# PowerClocks.net
KiCad netlist of a schematic drawn in Altium Designer
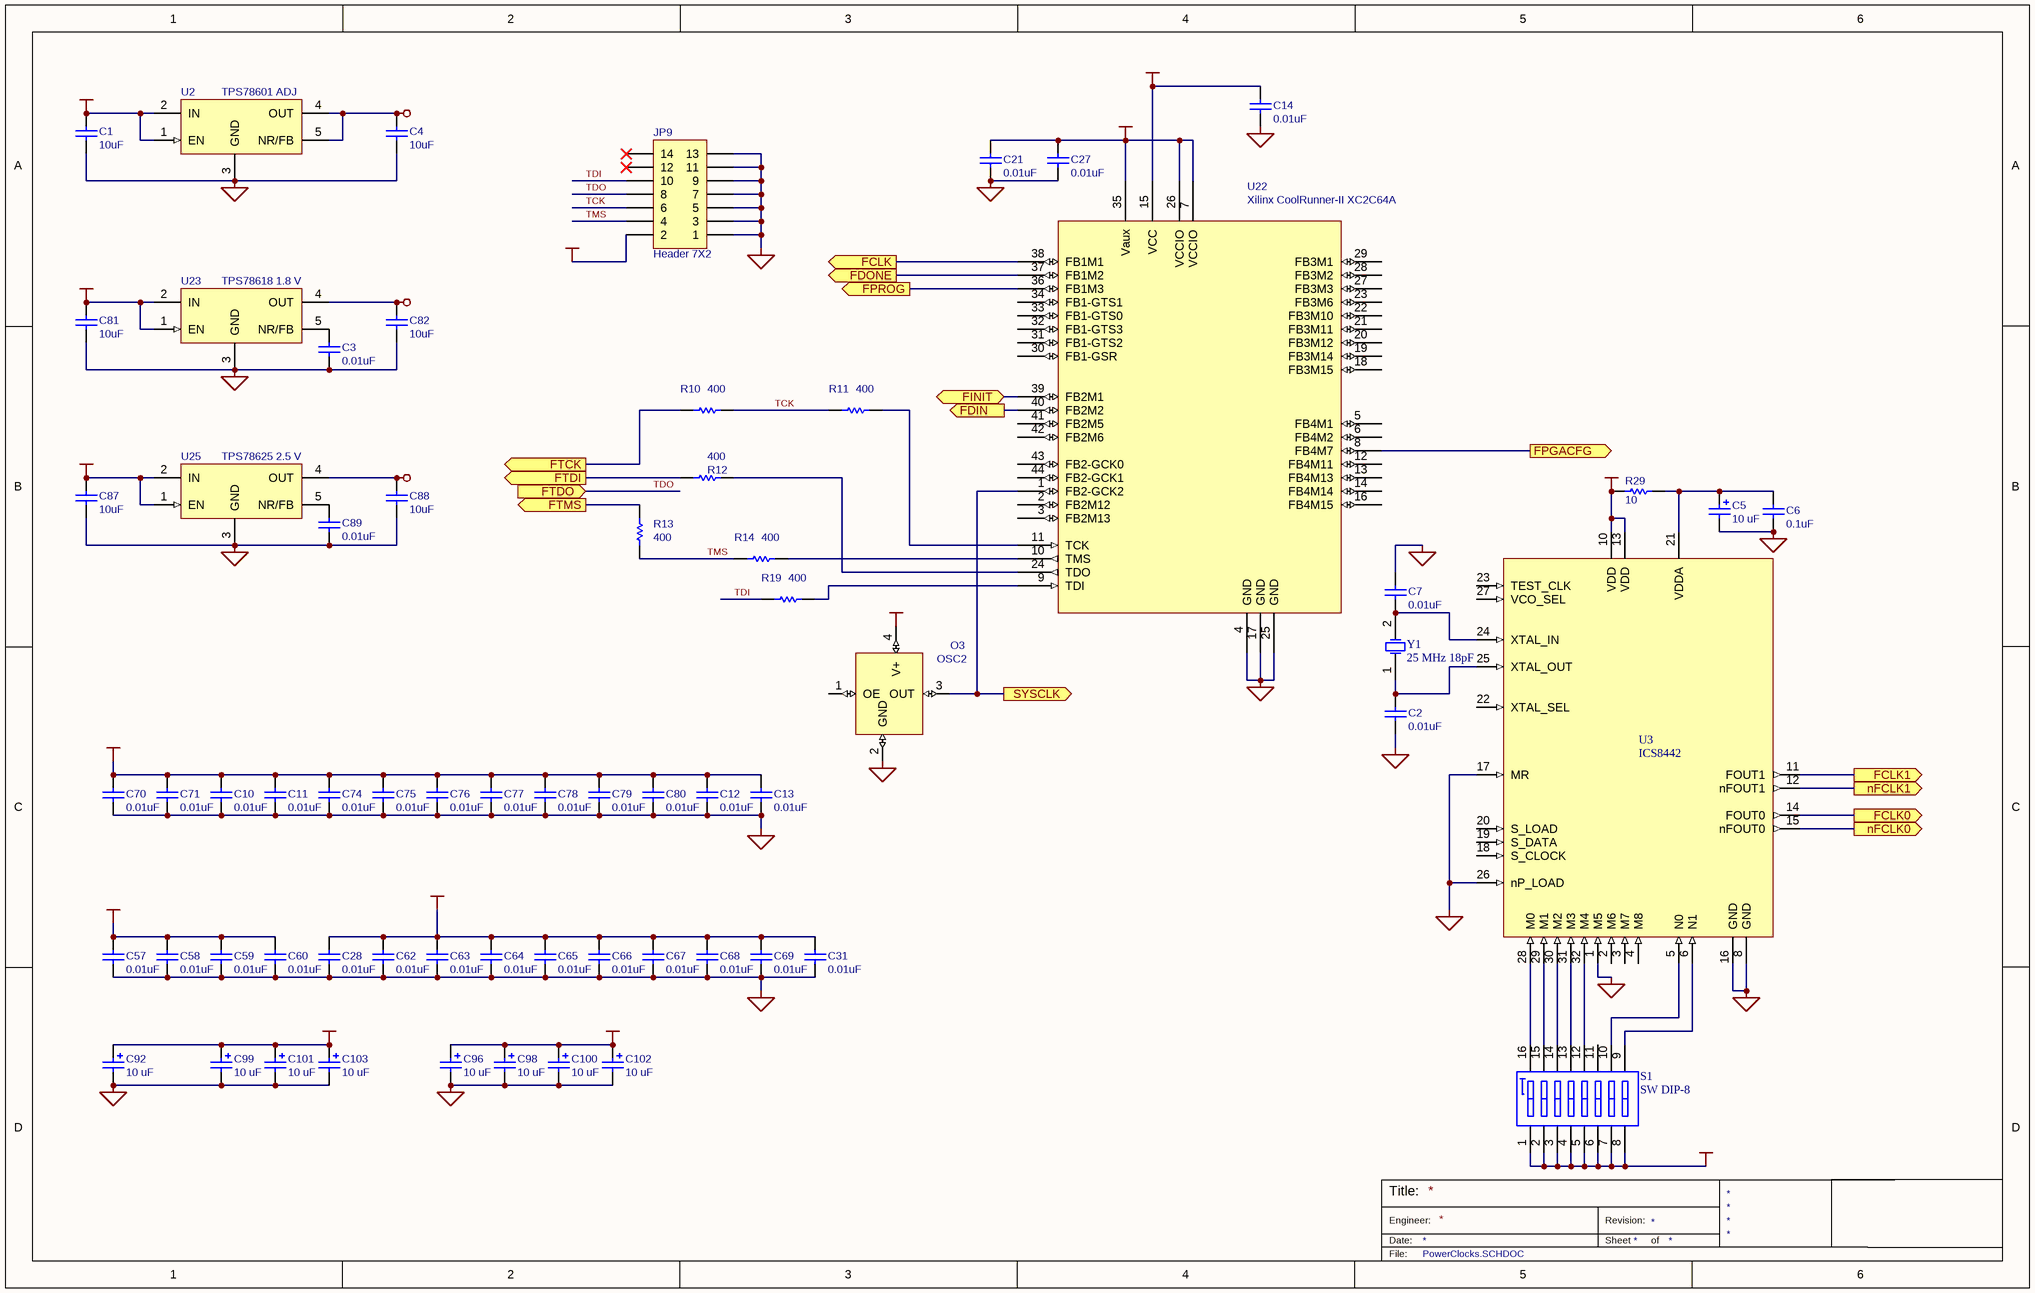
[diagram p0: PowerClocks.SCHDOC]

(export (version "E")
  (design (tool "Eeschema 10.0.6"))
  (components
    (comp (ref "C1")
      (value "10uF")
      (footprint "CC3216-1206")
      (description "Capacitor")
      (fields (field (name "PUBLISHER") "Altium Limited"))
      (libsource (lib "Miscellaneous Devices") (part "Cap"))
    )
    (comp (ref "C2")
      (value "0.01uF")
      (footprint "CC1005-0402")
      (description "Capacitor")
      (fields
        (field (name "MANUFACTURER") "Generic Components")
        (field (name "Comment") "Cap")
        (field (name "PUBLISHER") "Altium Limited")
      )
      (libsource (lib "Miscellaneous Devices") (part "Cap"))
    )
    (comp (ref "C3")
      (value "0.01uF")
      (footprint "CC1005-0402")
      (description "Capacitor")
      (fields (field (name "Comment") "Cap") (field (name "PUBLISHER") "Altium Limited"))
      (libsource (lib "Miscellaneous Devices") (part "Cap"))
    )
    (comp (ref "C4")
      (value "10uF")
      (footprint "CC3216-1206")
      (description "Capacitor")
      (fields (field (name "PUBLISHER") "Altium Limited"))
      (libsource (lib "Miscellaneous Devices") (part "Cap"))
    )
    (comp (ref "C5")
      (value "10 uF")
      (footprint "TC3528-1411")
      (description "Tantalum Bypass cap")
      (fields
        (field (name "MANUFACTURER") "Generic Components")
        (field (name "Comment") "Bypass Cap")
        (field (name "PUBLISHER") "Altium Limited")
      )
      (libsource (lib "Miscellaneous Devices") (part "Cap Pol3"))
    )
    (comp (ref "C6")
      (value "0.1uF")
      (footprint "CC1005-0402")
      (description "Capacitor")
      (fields
        (field (name "MANUFACTURER") "Generic Components")
        (field (name "Comment") "Cap")
        (field (name "PUBLISHER") "Altium Limited")
      )
      (libsource (lib "Miscellaneous Devices") (part "Cap"))
    )
    (comp (ref "C7")
      (value "0.01uF")
      (footprint "CC1005-0402")
      (description "Capacitor")
      (fields
        (field (name "MANUFACTURER") "Generic Components")
        (field (name "Comment") "Cap")
        (field (name "PUBLISHER") "Altium Limited")
      )
      (libsource (lib "Miscellaneous Devices") (part "Cap"))
    )
    (comp (ref "C10")
      (value "0.01uF")
      (footprint "CC1005-0402")
      (description "Capacitor")
      (fields
        (field (name "MANUFACTURER") "Generic Components")
        (field (name "Comment") "Cap")
        (field (name "PUBLISHER") "Altium Limited")
      )
      (libsource (lib "Miscellaneous Devices") (part "Cap"))
    )
    (comp (ref "C11")
      (value "0.01uF")
      (footprint "CC1005-0402")
      (description "Capacitor")
      (fields
        (field (name "MANUFACTURER") "Generic Components")
        (field (name "Comment") "Cap")
        (field (name "PUBLISHER") "Altium Limited")
      )
      (libsource (lib "Miscellaneous Devices") (part "Cap"))
    )
    (comp (ref "C12")
      (value "0.01uF")
      (footprint "CC1005-0402")
      (description "Capacitor")
      (fields
        (field (name "MANUFACTURER") "Generic Components")
        (field (name "Comment") "Cap")
        (field (name "PUBLISHER") "Altium Limited")
      )
      (libsource (lib "Miscellaneous Devices") (part "Cap"))
    )
    (comp (ref "C13")
      (value "0.01uF")
      (footprint "CC1005-0402")
      (description "Capacitor")
      (fields
        (field (name "MANUFACTURER") "Generic Components")
        (field (name "Comment") "Cap")
        (field (name "PUBLISHER") "Altium Limited")
      )
      (libsource (lib "Miscellaneous Devices") (part "Cap"))
    )
    (comp (ref "C14")
      (value "0.01uF")
      (footprint "CC1005-0402")
      (description "Capacitor")
      (fields
        (field (name "MANUFACTURER") "Generic Components")
        (field (name "Comment") "Cap")
        (field (name "PUBLISHER") "Altium Limited")
      )
      (libsource (lib "Miscellaneous Devices") (part "Cap"))
    )
    (comp (ref "C21")
      (value "0.01uF")
      (footprint "CC1005-0402")
      (description "Capacitor")
      (fields
        (field (name "MANUFACTURER") "Generic Components")
        (field (name "Comment") "Cap")
        (field (name "PUBLISHER") "Altium Limited")
      )
      (libsource (lib "Miscellaneous Devices") (part "Cap"))
    )
    (comp (ref "C27")
      (value "0.01uF")
      (footprint "CC1005-0402")
      (description "Capacitor")
      (fields
        (field (name "MANUFACTURER") "Generic Components")
        (field (name "Comment") "Cap")
        (field (name "PUBLISHER") "Altium Limited")
      )
      (libsource (lib "Miscellaneous Devices") (part "Cap"))
    )
    (comp (ref "C28")
      (value "0.01uF")
      (footprint "CC1005-0402")
      (description "Capacitor")
      (fields
        (field (name "MANUFACTURER") "Generic Components")
        (field (name "Comment") "Cap")
        (field (name "PUBLISHER") "Altium Limited")
      )
      (libsource (lib "Miscellaneous Devices") (part "Cap"))
    )
    (comp (ref "C31")
      (value "0.01uF")
      (footprint "CC1005-0402")
      (description "Capacitor")
      (fields
        (field (name "MANUFACTURER") "Generic Components")
        (field (name "Comment") "Cap")
        (field (name "PUBLISHER") "Altium Limited")
      )
      (libsource (lib "Miscellaneous Devices") (part "Cap"))
    )
    (comp (ref "C57")
      (value "0.01uF")
      (footprint "CC1005-0402")
      (description "Capacitor")
      (fields
        (field (name "MANUFACTURER") "Generic Components")
        (field (name "Comment") "Cap")
        (field (name "PUBLISHER") "Altium Limited")
      )
      (libsource (lib "Miscellaneous Devices") (part "Cap"))
    )
    (comp (ref "C58")
      (value "0.01uF")
      (footprint "CC1005-0402")
      (description "Capacitor")
      (fields
        (field (name "MANUFACTURER") "Generic Components")
        (field (name "Comment") "Cap")
        (field (name "PUBLISHER") "Altium Limited")
      )
      (libsource (lib "Miscellaneous Devices") (part "Cap"))
    )
    (comp (ref "C59")
      (value "0.01uF")
      (footprint "CC1005-0402")
      (description "Capacitor")
      (fields
        (field (name "MANUFACTURER") "Generic Components")
        (field (name "Comment") "Cap")
        (field (name "PUBLISHER") "Altium Limited")
      )
      (libsource (lib "Miscellaneous Devices") (part "Cap"))
    )
    (comp (ref "C60")
      (value "0.01uF")
      (footprint "CC1005-0402")
      (description "Capacitor")
      (fields
        (field (name "MANUFACTURER") "Generic Components")
        (field (name "Comment") "Cap")
        (field (name "PUBLISHER") "Altium Limited")
      )
      (libsource (lib "Miscellaneous Devices") (part "Cap"))
    )
    (comp (ref "C62")
      (value "0.01uF")
      (footprint "CC1005-0402")
      (description "Capacitor")
      (fields
        (field (name "MANUFACTURER") "Generic Components")
        (field (name "Comment") "Cap")
        (field (name "PUBLISHER") "Altium Limited")
      )
      (libsource (lib "Miscellaneous Devices") (part "Cap"))
    )
    (comp (ref "C63")
      (value "0.01uF")
      (footprint "CC1005-0402")
      (description "Capacitor")
      (fields
        (field (name "MANUFACTURER") "Generic Components")
        (field (name "Comment") "Cap")
        (field (name "PUBLISHER") "Altium Limited")
      )
      (libsource (lib "Miscellaneous Devices") (part "Cap"))
    )
    (comp (ref "C64")
      (value "0.01uF")
      (footprint "CC1005-0402")
      (description "Capacitor")
      (fields
        (field (name "MANUFACTURER") "Generic Components")
        (field (name "Comment") "Cap")
        (field (name "PUBLISHER") "Altium Limited")
      )
      (libsource (lib "Miscellaneous Devices") (part "Cap"))
    )
    (comp (ref "C65")
      (value "0.01uF")
      (footprint "CC1005-0402")
      (description "Capacitor")
      (fields
        (field (name "MANUFACTURER") "Generic Components")
        (field (name "Comment") "Cap")
        (field (name "PUBLISHER") "Altium Limited")
      )
      (libsource (lib "Miscellaneous Devices") (part "Cap"))
    )
    (comp (ref "C66")
      (value "0.01uF")
      (footprint "CC1005-0402")
      (description "Capacitor")
      (fields
        (field (name "MANUFACTURER") "Generic Components")
        (field (name "Comment") "Cap")
        (field (name "PUBLISHER") "Altium Limited")
      )
      (libsource (lib "Miscellaneous Devices") (part "Cap"))
    )
    (comp (ref "C67")
      (value "0.01uF")
      (footprint "CC1005-0402")
      (description "Capacitor")
      (fields
        (field (name "MANUFACTURER") "Generic Components")
        (field (name "Comment") "Cap")
        (field (name "PUBLISHER") "Altium Limited")
      )
      (libsource (lib "Miscellaneous Devices") (part "Cap"))
    )
    (comp (ref "C68")
      (value "0.01uF")
      (footprint "CC1005-0402")
      (description "Capacitor")
      (fields
        (field (name "MANUFACTURER") "Generic Components")
        (field (name "Comment") "Cap")
        (field (name "PUBLISHER") "Altium Limited")
      )
      (libsource (lib "Miscellaneous Devices") (part "Cap"))
    )
    (comp (ref "C69")
      (value "0.01uF")
      (footprint "CC1005-0402")
      (description "Capacitor")
      (fields
        (field (name "MANUFACTURER") "Generic Components")
        (field (name "Comment") "Cap")
        (field (name "PUBLISHER") "Altium Limited")
      )
      (libsource (lib "Miscellaneous Devices") (part "Cap"))
    )
    (comp (ref "C70")
      (value "0.01uF")
      (footprint "CC1005-0402")
      (description "Capacitor")
      (fields
        (field (name "MANUFACTURER") "Generic Components")
        (field (name "Comment") "Cap")
        (field (name "PUBLISHER") "Altium Limited")
      )
      (libsource (lib "Miscellaneous Devices") (part "Cap"))
    )
    (comp (ref "C71")
      (value "0.01uF")
      (footprint "CC1005-0402")
      (description "Capacitor")
      (fields
        (field (name "MANUFACTURER") "Generic Components")
        (field (name "Comment") "Cap")
        (field (name "PUBLISHER") "Altium Limited")
      )
      (libsource (lib "Miscellaneous Devices") (part "Cap"))
    )
    (comp (ref "C74")
      (value "0.01uF")
      (footprint "CC1005-0402")
      (description "Capacitor")
      (fields
        (field (name "MANUFACTURER") "Generic Components")
        (field (name "Comment") "Cap")
        (field (name "PUBLISHER") "Altium Limited")
      )
      (libsource (lib "Miscellaneous Devices") (part "Cap"))
    )
    (comp (ref "C75")
      (value "0.01uF")
      (footprint "CC1005-0402")
      (description "Capacitor")
      (fields
        (field (name "MANUFACTURER") "Generic Components")
        (field (name "Comment") "Cap")
        (field (name "PUBLISHER") "Altium Limited")
      )
      (libsource (lib "Miscellaneous Devices") (part "Cap"))
    )
    (comp (ref "C76")
      (value "0.01uF")
      (footprint "CC1005-0402")
      (description "Capacitor")
      (fields
        (field (name "MANUFACTURER") "Generic Components")
        (field (name "Comment") "Cap")
        (field (name "PUBLISHER") "Altium Limited")
      )
      (libsource (lib "Miscellaneous Devices") (part "Cap"))
    )
    (comp (ref "C77")
      (value "0.01uF")
      (footprint "CC1005-0402")
      (description "Capacitor")
      (fields
        (field (name "MANUFACTURER") "Generic Components")
        (field (name "Comment") "Cap")
        (field (name "PUBLISHER") "Altium Limited")
      )
      (libsource (lib "Miscellaneous Devices") (part "Cap"))
    )
    (comp (ref "C78")
      (value "0.01uF")
      (footprint "CC1005-0402")
      (description "Capacitor")
      (fields
        (field (name "MANUFACTURER") "Generic Components")
        (field (name "Comment") "Cap")
        (field (name "PUBLISHER") "Altium Limited")
      )
      (libsource (lib "Miscellaneous Devices") (part "Cap"))
    )
    (comp (ref "C79")
      (value "0.01uF")
      (footprint "CC1005-0402")
      (description "Capacitor")
      (fields
        (field (name "MANUFACTURER") "Generic Components")
        (field (name "Comment") "Cap")
        (field (name "PUBLISHER") "Altium Limited")
      )
      (libsource (lib "Miscellaneous Devices") (part "Cap"))
    )
    (comp (ref "C80")
      (value "0.01uF")
      (footprint "CC1005-0402")
      (description "Capacitor")
      (fields
        (field (name "MANUFACTURER") "Generic Components")
        (field (name "Comment") "Cap")
        (field (name "PUBLISHER") "Altium Limited")
      )
      (libsource (lib "Miscellaneous Devices") (part "Cap"))
    )
    (comp (ref "C81")
      (value "10uF")
      (footprint "CC3216-1206")
      (description "Capacitor")
      (fields (field (name "PUBLISHER") "Altium Limited"))
      (libsource (lib "Miscellaneous Devices") (part "Cap"))
    )
    (comp (ref "C82")
      (value "10uF")
      (footprint "CC3216-1206")
      (description "Capacitor")
      (fields (field (name "PUBLISHER") "Altium Limited"))
      (libsource (lib "Miscellaneous Devices") (part "Cap"))
    )
    (comp (ref "C87")
      (value "10uF")
      (footprint "CC3216-1206")
      (description "Capacitor")
      (fields (field (name "PUBLISHER") "Altium Limited"))
      (libsource (lib "Miscellaneous Devices") (part "Cap"))
    )
    (comp (ref "C88")
      (value "10uF")
      (footprint "CC3216-1206")
      (description "Capacitor")
      (fields (field (name "PUBLISHER") "Altium Limited"))
      (libsource (lib "Miscellaneous Devices") (part "Cap"))
    )
    (comp (ref "C89")
      (value "0.01uF")
      (footprint "CC1005-0402")
      (description "Capacitor")
      (fields (field (name "Comment") "Cap") (field (name "PUBLISHER") "Altium Limited"))
      (libsource (lib "Miscellaneous Devices") (part "Cap"))
    )
    (comp (ref "C92")
      (value "10 uF")
      (footprint "TC3528-1411")
      (description "Tantalum Bypass cap")
      (fields
        (field (name "MANUFACTURER") "Generic Components")
        (field (name "Comment") "Bypass Cap")
        (field (name "PUBLISHER") "Altium Limited")
      )
      (libsource (lib "Miscellaneous Devices") (part "Cap Pol3"))
    )
    (comp (ref "C96")
      (value "10 uF")
      (footprint "TC3528-1411")
      (description "Tantalum Bypass cap")
      (fields
        (field (name "MANUFACTURER") "Generic Components")
        (field (name "Comment") "Bypass Cap")
        (field (name "PUBLISHER") "Altium Limited")
      )
      (libsource (lib "Miscellaneous Devices") (part "Cap Pol3"))
    )
    (comp (ref "C98")
      (value "10 uF")
      (footprint "TC3528-1411")
      (description "Tantalum Bypass cap")
      (fields
        (field (name "MANUFACTURER") "Generic Components")
        (field (name "Comment") "Bypass Cap")
        (field (name "PUBLISHER") "Altium Limited")
      )
      (libsource (lib "Miscellaneous Devices") (part "Cap Pol3"))
    )
    (comp (ref "C99")
      (value "10 uF")
      (footprint "TC3528-1411")
      (description "Tantalum Bypass cap")
      (fields
        (field (name "MANUFACTURER") "Generic Components")
        (field (name "Comment") "Bypass Cap")
        (field (name "PUBLISHER") "Altium Limited")
      )
      (libsource (lib "Miscellaneous Devices") (part "Cap Pol3"))
    )
    (comp (ref "C100")
      (value "10 uF")
      (footprint "TC3528-1411")
      (description "Tantalum Bypass cap")
      (fields
        (field (name "MANUFACTURER") "Generic Components")
        (field (name "Comment") "Bypass Cap")
        (field (name "PUBLISHER") "Altium Limited")
      )
      (libsource (lib "Miscellaneous Devices") (part "Cap Pol3"))
    )
    (comp (ref "C101")
      (value "10 uF")
      (footprint "TC3528-1411")
      (description "Tantalum Bypass cap")
      (fields
        (field (name "MANUFACTURER") "Generic Components")
        (field (name "Comment") "Bypass Cap")
        (field (name "PUBLISHER") "Altium Limited")
      )
      (libsource (lib "Miscellaneous Devices") (part "Cap Pol3"))
    )
    (comp (ref "C102")
      (value "10 uF")
      (footprint "TC3528-1411")
      (description "Tantalum Bypass cap")
      (fields
        (field (name "MANUFACTURER") "Generic Components")
        (field (name "Comment") "Bypass Cap")
        (field (name "PUBLISHER") "Altium Limited")
      )
      (libsource (lib "Miscellaneous Devices") (part "Cap Pol3"))
    )
    (comp (ref "C103")
      (value "10 uF")
      (footprint "TC3528-1411")
      (description "Tantalum Bypass cap")
      (fields
        (field (name "MANUFACTURER") "Generic Components")
        (field (name "Comment") "Bypass Cap")
        (field (name "PUBLISHER") "Altium Limited")
      )
      (libsource (lib "Miscellaneous Devices") (part "Cap Pol3"))
    )
    (comp (ref "JP9")
      (value "Header 7X2")
      (footprint "HDR2x7-2mm")
      (description "Header, 7-Pin, Dual row")
      (fields (field (name "MANUFACTURER") "Generic Components") (field (name "PUBLISHER") "Altium Limited"))
      (libsource (lib "Miscellaneous Connectors") (part "Header 7X2"))
    )
    (comp (ref "O3")
      (value "OSC2")
      (footprint "ECS-3953M")
      (description "ECS SMD Oscillator, ECS-3953M")
      (libsource (lib "parts") (part "OSC2"))
    )
    (comp (ref "R10")
      (value "400")
      (footprint "CR1608-0603")
      (description "Resistor")
      (fields
        (field (name "MANUFACTURER") "Generic Components")
        (field (name "Comment") "current-limiting series res")
        (field (name "PUBLISHER") "Altium Limited")
      )
      (libsource (lib "Miscellaneous Devices") (part "Res1"))
    )
    (comp (ref "R11")
      (value "400")
      (footprint "CR1608-0603")
      (description "Resistor")
      (fields
        (field (name "MANUFACTURER") "Generic Components")
        (field (name "Comment") "current-limiting series res")
        (field (name "PUBLISHER") "Altium Limited")
      )
      (libsource (lib "Miscellaneous Devices") (part "Res1"))
    )
    (comp (ref "R12")
      (value "400")
      (footprint "CR1608-0603")
      (description "Resistor")
      (fields
        (field (name "MANUFACTURER") "Generic Components")
        (field (name "Comment") "current-limiting series res")
        (field (name "PUBLISHER") "Altium Limited")
      )
      (libsource (lib "Miscellaneous Devices") (part "Res1"))
    )
    (comp (ref "R13")
      (value "400")
      (footprint "CR1608-0603")
      (description "Resistor")
      (fields
        (field (name "MANUFACTURER") "Generic Components")
        (field (name "Comment") "current-limiting series res")
        (field (name "PUBLISHER") "Altium Limited")
      )
      (libsource (lib "Miscellaneous Devices") (part "Res1"))
    )
    (comp (ref "R14")
      (value "400")
      (footprint "CR1608-0603")
      (description "Resistor")
      (fields
        (field (name "MANUFACTURER") "Generic Components")
        (field (name "Comment") "current-limiting series res")
        (field (name "PUBLISHER") "Altium Limited")
      )
      (libsource (lib "Miscellaneous Devices") (part "Res1"))
    )
    (comp (ref "R19")
      (value "400")
      (footprint "CR1608-0603")
      (description "Resistor")
      (fields
        (field (name "MANUFACTURER") "Generic Components")
        (field (name "Comment") "current-limiting series res")
        (field (name "PUBLISHER") "Altium Limited")
      )
      (libsource (lib "Miscellaneous Devices") (part "Res1"))
    )
    (comp (ref "R29")
      (value "10")
      (footprint "CR1608-0603")
      (description "Resistor")
      (fields
        (field (name "MANUFACTURER") "Generic Components")
        (field (name "Comment") "Res1")
        (field (name "PUBLISHER") "Altium Limited")
      )
      (libsource (lib "Miscellaneous Devices") (part "Res1"))
    )
    (comp (ref "S1")
      (value "SW DIP-8")
      (footprint "CANNON-SDA")
      (description "DIP Switch, 8 Position, SPST")
      (fields (field (name "PUBLISHER") "Altium Limited"))
      (libsource (lib "Miscellaneous Devices") (part "SW DIP-8"))
    )
    (comp (ref "U2")
      (value "TPS78601 ADJ")
      (footprint "KTT")
      (description "TI 1.5A LDO")
      (libsource (lib "parts") (part "TPS786XX"))
    )
    (comp (ref "U3")
      (value "ICS8442")
      (footprint "QFP7x7-G32/N")
      (description "700 MHx Crystal Oscillator-todifferential LVDS Freq Synth")
      (libsource (lib "parts") (part "ICS8442"))
    )
    (comp (ref "U22")
      (value "Xilinx CoolRunner-II XC2C64A")
      (footprint "QFP10x10-G44/G10N")
      (libsource (lib "parts") (part "XC2C64A-5VQ44C"))
    )
    (comp (ref "U23")
      (value "TPS78618 1.8 V")
      (footprint "KTT")
      (description "TI 1.5A LDO")
      (libsource (lib "parts") (part "TPS786XX"))
    )
    (comp (ref "U25")
      (value "TPS78625 2.5 V")
      (footprint "KTT")
      (description "TI 1.5A LDO")
      (libsource (lib "parts") (part "TPS786XX"))
    )
    (comp (ref "Y1")
      (value "25 MHz 18pF")
      (footprint "ECS CSM-7")
      (description "Crystal Oscillator")
      (fields (field (name "PUBLISHER") "Altium Limited"))
      (libsource (lib "Miscellaneous Devices") (part "XTAL"))
    )
  )
  (nets
    (net (code "1") (name "+1.2VCC") (class "Default")
      (node (ref "C100") (pin "1") (pinfunction "1_1") (pintype "passive"))
      (node (ref "C102") (pin "1") (pinfunction "1_1") (pintype "passive"))
      (node (ref "C4") (pin "2") (pinfunction "2_2") (pintype "passive"))
      (node (ref "C57") (pin "2") (pinfunction "2_2") (pintype "passive"))
      (node (ref "C58") (pin "2") (pinfunction "2_2") (pintype "passive"))
      (node (ref "C59") (pin "2") (pinfunction "2_2") (pintype "passive"))
      (node (ref "C60") (pin "2") (pinfunction "2_2") (pintype "passive"))
      (node (ref "C96") (pin "1") (pinfunction "1_1") (pintype "passive"))
      (node (ref "C98") (pin "1") (pinfunction "1_1") (pintype "passive"))
      (node (ref "U2") (pin "4") (pinfunction "OUT_4") (pintype "power_in"))
      (node (ref "U2") (pin "5") (pinfunction "NR/FB_5") (pintype "power_in"))
    )
    (net (code "2") (name "+1.8VCC") (class "Default")
      (node (ref "C14") (pin "2") (pinfunction "2_2") (pintype "passive"))
      (node (ref "C82") (pin "2") (pinfunction "2_2") (pintype "passive"))
      (node (ref "U22") (pin "15") (pinfunction "VCC_15") (pintype "power_in"))
      (node (ref "U23") (pin "4") (pinfunction "OUT_4") (pintype "power_in"))
    )
    (net (code "3") (name "+2.5VCC") (class "Default")
      (node (ref "C28") (pin "2") (pinfunction "2_2") (pintype "passive"))
      (node (ref "C31") (pin "2") (pinfunction "2_2") (pintype "passive"))
      (node (ref "C62") (pin "2") (pinfunction "2_2") (pintype "passive"))
      (node (ref "C63") (pin "2") (pinfunction "2_2") (pintype "passive"))
      (node (ref "C64") (pin "2") (pinfunction "2_2") (pintype "passive"))
      (node (ref "C65") (pin "2") (pinfunction "2_2") (pintype "passive"))
      (node (ref "C66") (pin "2") (pinfunction "2_2") (pintype "passive"))
      (node (ref "C67") (pin "2") (pinfunction "2_2") (pintype "passive"))
      (node (ref "C68") (pin "2") (pinfunction "2_2") (pintype "passive"))
      (node (ref "C69") (pin "2") (pinfunction "2_2") (pintype "passive"))
      (node (ref "C88") (pin "2") (pinfunction "2_2") (pintype "passive"))
      (node (ref "U25") (pin "4") (pinfunction "OUT_4") (pintype "power_in"))
    )
    (net (code "4") (name "/FCLK") (class "Default")
      (node (ref "U22") (pin "38") (pinfunction "FB1M1_38") (pintype "bidirectional"))
    )
    (net (code "5") (name "/FCLK0") (class "Default")
      (node (ref "U3") (pin "14") (pinfunction "FOUT0_14") (pintype "output"))
    )
    (net (code "6") (name "/FCLK1") (class "Default")
      (node (ref "U3") (pin "11") (pinfunction "FOUT1_11") (pintype "output"))
    )
    (net (code "7") (name "/FDIN") (class "Default")
      (node (ref "U22") (pin "40") (pinfunction "FB2M2_40") (pintype "bidirectional"))
    )
    (net (code "8") (name "/FDONE") (class "Default")
      (node (ref "U22") (pin "37") (pinfunction "FB1M2_37") (pintype "bidirectional"))
    )
    (net (code "9") (name "/FINIT") (class "Default")
      (node (ref "U22") (pin "39") (pinfunction "FB2M1_39") (pintype "bidirectional"))
    )
    (net (code "10") (name "/FPGACFG") (class "Default")
      (node (ref "U22") (pin "8") (pinfunction "FB4M7_8") (pintype "bidirectional"))
    )
    (net (code "11") (name "/FPROG") (class "Default")
      (node (ref "U22") (pin "36") (pinfunction "FB1M3_36") (pintype "bidirectional"))
    )
    (net (code "12") (name "/FTCK") (class "Default")
      (node (ref "R10") (pin "2") (pinfunction "2_2") (pintype "passive"))
    )
    (net (code "13") (name "/FTDI") (class "Default")
      (node (ref "R12") (pin "2") (pinfunction "2_2") (pintype "passive"))
    )
    (net (code "14") (name "/FTMS") (class "Default")
      (node (ref "R13") (pin "1") (pinfunction "1_1") (pintype "passive"))
    )
    (net (code "15") (name "/SYSCLK") (class "Default")
      (node (ref "O3") (pin "3") (pinfunction "OUT_3") (pintype "bidirectional"))
      (node (ref "U22") (pin "1") (pinfunction "FB2-GCK2_1") (pintype "bidirectional"))
    )
    (net (code "16") (name "/TCK") (class "Default")
      (node (ref "JP9") (pin "6") (pinfunction "6_6") (pintype "passive"))
      (node (ref "R10") (pin "1") (pinfunction "1_1") (pintype "passive"))
      (node (ref "R11") (pin "2") (pinfunction "2_2") (pintype "passive"))
    )
    (net (code "17") (name "/TDI") (class "Default")
      (node (ref "JP9") (pin "10") (pinfunction "10_10") (pintype "passive"))
      (node (ref "R19") (pin "2") (pinfunction "2_2") (pintype "passive"))
    )
    (net (code "18") (name "/TDO") (class "Default")
      (node (ref "JP9") (pin "8") (pinfunction "8_8") (pintype "passive"))
    )
    (net (code "19") (name "/TMS") (class "Default")
      (node (ref "JP9") (pin "4") (pinfunction "4_4") (pintype "passive"))
      (node (ref "R13") (pin "2") (pinfunction "2_2") (pintype "passive"))
      (node (ref "R14") (pin "2") (pinfunction "2_2") (pintype "passive"))
    )
    (net (code "20") (name "/nFCLK0") (class "Default")
      (node (ref "U3") (pin "15") (pinfunction "nFOUT0_15") (pintype "output"))
    )
    (net (code "21") (name "/nFCLK1") (class "Default")
      (node (ref "U3") (pin "12") (pinfunction "nFOUT1_12") (pintype "output"))
    )
    (net (code "22") (name "GND") (class "Default")
      (node (ref "C1") (pin "1") (pinfunction "1_1") (pintype "passive"))
      (node (ref "C10") (pin "1") (pinfunction "1_1") (pintype "passive"))
      (node (ref "C100") (pin "2") (pinfunction "2_2") (pintype "passive"))
      (node (ref "C101") (pin "2") (pinfunction "2_2") (pintype "passive"))
      (node (ref "C102") (pin "2") (pinfunction "2_2") (pintype "passive"))
      (node (ref "C103") (pin "2") (pinfunction "2_2") (pintype "passive"))
      (node (ref "C11") (pin "1") (pinfunction "1_1") (pintype "passive"))
      (node (ref "C12") (pin "1") (pinfunction "1_1") (pintype "passive"))
      (node (ref "C13") (pin "1") (pinfunction "1_1") (pintype "passive"))
      (node (ref "C14") (pin "1") (pinfunction "1_1") (pintype "passive"))
      (node (ref "C2") (pin "1") (pinfunction "1_1") (pintype "passive"))
      (node (ref "C21") (pin "1") (pinfunction "1_1") (pintype "passive"))
      (node (ref "C27") (pin "1") (pinfunction "1_1") (pintype "passive"))
      (node (ref "C28") (pin "1") (pinfunction "1_1") (pintype "passive"))
      (node (ref "C3") (pin "2") (pinfunction "2_2") (pintype "passive"))
      (node (ref "C31") (pin "1") (pinfunction "1_1") (pintype "passive"))
      (node (ref "C4") (pin "1") (pinfunction "1_1") (pintype "passive"))
      (node (ref "C5") (pin "2") (pinfunction "2_2") (pintype "passive"))
      (node (ref "C57") (pin "1") (pinfunction "1_1") (pintype "passive"))
      (node (ref "C58") (pin "1") (pinfunction "1_1") (pintype "passive"))
      (node (ref "C59") (pin "1") (pinfunction "1_1") (pintype "passive"))
      (node (ref "C6") (pin "1") (pinfunction "1_1") (pintype "passive"))
      (node (ref "C60") (pin "1") (pinfunction "1_1") (pintype "passive"))
      (node (ref "C62") (pin "1") (pinfunction "1_1") (pintype "passive"))
      (node (ref "C63") (pin "1") (pinfunction "1_1") (pintype "passive"))
      (node (ref "C64") (pin "1") (pinfunction "1_1") (pintype "passive"))
      (node (ref "C65") (pin "1") (pinfunction "1_1") (pintype "passive"))
      (node (ref "C66") (pin "1") (pinfunction "1_1") (pintype "passive"))
      (node (ref "C67") (pin "1") (pinfunction "1_1") (pintype "passive"))
      (node (ref "C68") (pin "1") (pinfunction "1_1") (pintype "passive"))
      (node (ref "C69") (pin "1") (pinfunction "1_1") (pintype "passive"))
      (node (ref "C7") (pin "2") (pinfunction "2_2") (pintype "passive"))
      (node (ref "C70") (pin "1") (pinfunction "1_1") (pintype "passive"))
      (node (ref "C71") (pin "1") (pinfunction "1_1") (pintype "passive"))
      (node (ref "C74") (pin "1") (pinfunction "1_1") (pintype "passive"))
      (node (ref "C75") (pin "1") (pinfunction "1_1") (pintype "passive"))
      (node (ref "C76") (pin "1") (pinfunction "1_1") (pintype "passive"))
      (node (ref "C77") (pin "1") (pinfunction "1_1") (pintype "passive"))
      (node (ref "C78") (pin "1") (pinfunction "1_1") (pintype "passive"))
      (node (ref "C79") (pin "1") (pinfunction "1_1") (pintype "passive"))
      (node (ref "C80") (pin "1") (pinfunction "1_1") (pintype "passive"))
      (node (ref "C81") (pin "1") (pinfunction "1_1") (pintype "passive"))
      (node (ref "C82") (pin "1") (pinfunction "1_1") (pintype "passive"))
      (node (ref "C87") (pin "1") (pinfunction "1_1") (pintype "passive"))
      (node (ref "C88") (pin "1") (pinfunction "1_1") (pintype "passive"))
      (node (ref "C89") (pin "2") (pinfunction "2_2") (pintype "passive"))
      (node (ref "C92") (pin "2") (pinfunction "2_2") (pintype "passive"))
      (node (ref "C96") (pin "2") (pinfunction "2_2") (pintype "passive"))
      (node (ref "C98") (pin "2") (pinfunction "2_2") (pintype "passive"))
      (node (ref "C99") (pin "2") (pinfunction "2_2") (pintype "passive"))
      (node (ref "JP9") (pin "1") (pinfunction "1_1") (pintype "passive"))
      (node (ref "JP9") (pin "11") (pinfunction "11_11") (pintype "passive"))
      (node (ref "JP9") (pin "13") (pinfunction "13_13") (pintype "passive"))
      (node (ref "JP9") (pin "3") (pinfunction "3_3") (pintype "passive"))
      (node (ref "JP9") (pin "5") (pinfunction "5_5") (pintype "passive"))
      (node (ref "JP9") (pin "7") (pinfunction "7_7") (pintype "passive"))
      (node (ref "JP9") (pin "9") (pinfunction "9_9") (pintype "passive"))
      (node (ref "O3") (pin "2") (pinfunction "GND_2") (pintype "bidirectional"))
      (node (ref "U2") (pin "3") (pinfunction "GND_3") (pintype "power_in"))
      (node (ref "U22") (pin "17") (pinfunction "GND_17") (pintype "power_in"))
      (node (ref "U22") (pin "25") (pinfunction "GND_25") (pintype "power_in"))
      (node (ref "U22") (pin "4") (pinfunction "GND_4") (pintype "power_in"))
      (node (ref "U23") (pin "3") (pinfunction "GND_3") (pintype "power_in"))
      (node (ref "U25") (pin "3") (pinfunction "GND_3") (pintype "power_in"))
      (node (ref "U3") (pin "1") (pinfunction "M5_1") (pintype "input"))
      (node (ref "U3") (pin "16") (pinfunction "GND_16") (pintype "power_in"))
      (node (ref "U3") (pin "17") (pinfunction "MR_17") (pintype "input"))
      (node (ref "U3") (pin "26") (pinfunction "nP_LOAD_26") (pintype "input"))
      (node (ref "U3") (pin "8") (pinfunction "GND_8") (pintype "power_in"))
    )
    (net (code "23") (name "Net-(S1-B1)") (class "Default")
      (node (ref "S1") (pin "16") (pinfunction "B1_16") (pintype "passive"))
      (node (ref "U3") (pin "28") (pinfunction "M0_28") (pintype "input"))
    )
    (net (code "24") (name "Net-(S1-B2)") (class "Default")
      (node (ref "S1") (pin "15") (pinfunction "B2_15") (pintype "passive"))
      (node (ref "U3") (pin "29") (pinfunction "M1_29") (pintype "input"))
    )
    (net (code "25") (name "Net-(S1-B3)") (class "Default")
      (node (ref "S1") (pin "14") (pinfunction "B3_14") (pintype "passive"))
      (node (ref "U3") (pin "30") (pinfunction "M2_30") (pintype "input"))
    )
    (net (code "26") (name "Net-(S1-B4)") (class "Default")
      (node (ref "S1") (pin "13") (pinfunction "B4_13") (pintype "passive"))
      (node (ref "U3") (pin "31") (pinfunction "M3_31") (pintype "input"))
    )
    (net (code "27") (name "Net-(S1-B5)") (class "Default")
      (node (ref "S1") (pin "12") (pinfunction "B5_12") (pintype "passive"))
      (node (ref "U3") (pin "32") (pinfunction "M4_32") (pintype "input"))
    )
    (net (code "28") (name "Net-(S1-B7)") (class "Default")
      (node (ref "S1") (pin "10") (pinfunction "B7_10") (pintype "passive"))
      (node (ref "U3") (pin "5") (pinfunction "N0_5") (pintype "input"))
    )
    (net (code "29") (name "Net-(S1-B8)") (class "Default")
      (node (ref "S1") (pin "9") (pinfunction "B8_9") (pintype "passive"))
      (node (ref "U3") (pin "6") (pinfunction "N1_6") (pintype "input"))
    )
    (net (code "30") (name "Net-(U3-VDDA)") (class "Default")
      (node (ref "C5") (pin "1") (pinfunction "1_1") (pintype "passive"))
      (node (ref "C6") (pin "2") (pinfunction "2_2") (pintype "passive"))
      (node (ref "R29") (pin "2") (pinfunction "2_2") (pintype "passive"))
      (node (ref "U3") (pin "21") (pinfunction "VDDA_21") (pintype "power_in"))
    )
    (net (code "31") (name "Net-(U3-XTAL_IN)") (class "Default")
      (node (ref "C7") (pin "1") (pinfunction "1_1") (pintype "passive"))
      (node (ref "U3") (pin "24") (pinfunction "XTAL_IN_24") (pintype "input"))
      (node (ref "Y1") (pin "2") (pinfunction "OSC2_2") (pintype "passive"))
    )
    (net (code "32") (name "Net-(U3-XTAL_OUT)") (class "Default")
      (node (ref "C2") (pin "2") (pinfunction "2_2") (pintype "passive"))
      (node (ref "U3") (pin "25") (pinfunction "XTAL_OUT_25") (pintype "input"))
      (node (ref "Y1") (pin "1") (pinfunction "OSC1_1") (pintype "passive"))
    )
    (net (code "33") (name "Net-(U22-TCK)") (class "Default")
      (node (ref "R11") (pin "1") (pinfunction "1_1") (pintype "passive"))
      (node (ref "U22") (pin "11") (pinfunction "TCK_11") (pintype "input"))
    )
    (net (code "34") (name "Net-(U22-TDI)") (class "Default")
      (node (ref "R19") (pin "1") (pinfunction "1_1") (pintype "passive"))
      (node (ref "U22") (pin "9") (pinfunction "TDI_9") (pintype "input"))
    )
    (net (code "35") (name "Net-(U22-TDO)") (class "Default")
      (node (ref "R12") (pin "1") (pinfunction "1_1") (pintype "passive"))
      (node (ref "U22") (pin "24") (pinfunction "TDO_24") (pintype "output"))
    )
    (net (code "36") (name "Net-(U22-TMS)") (class "Default")
      (node (ref "R14") (pin "1") (pinfunction "1_1") (pintype "passive"))
      (node (ref "U22") (pin "10") (pinfunction "TMS_10") (pintype "output"))
    )
    (net (code "37") (name "Net-(U23-NR{slash}FB)") (class "Default")
      (node (ref "C3") (pin "1") (pinfunction "1_1") (pintype "passive"))
      (node (ref "U23") (pin "5") (pinfunction "NR/FB_5") (pintype "power_in"))
    )
    (net (code "38") (name "Net-(U25-NR{slash}FB)") (class "Default")
      (node (ref "C89") (pin "1") (pinfunction "1_1") (pintype "passive"))
      (node (ref "U25") (pin "5") (pinfunction "NR/FB_5") (pintype "power_in"))
    )
    (net (code "39") (name "VCC") (class "Default")
      (node (ref "C1") (pin "2") (pinfunction "2_2") (pintype "passive"))
      (node (ref "C10") (pin "2") (pinfunction "2_2") (pintype "passive"))
      (node (ref "C101") (pin "1") (pinfunction "1_1") (pintype "passive"))
      (node (ref "C103") (pin "1") (pinfunction "1_1") (pintype "passive"))
      (node (ref "C11") (pin "2") (pinfunction "2_2") (pintype "passive"))
      (node (ref "C12") (pin "2") (pinfunction "2_2") (pintype "passive"))
      (node (ref "C13") (pin "2") (pinfunction "2_2") (pintype "passive"))
      (node (ref "C21") (pin "2") (pinfunction "2_2") (pintype "passive"))
      (node (ref "C27") (pin "2") (pinfunction "2_2") (pintype "passive"))
      (node (ref "C70") (pin "2") (pinfunction "2_2") (pintype "passive"))
      (node (ref "C71") (pin "2") (pinfunction "2_2") (pintype "passive"))
      (node (ref "C74") (pin "2") (pinfunction "2_2") (pintype "passive"))
      (node (ref "C75") (pin "2") (pinfunction "2_2") (pintype "passive"))
      (node (ref "C76") (pin "2") (pinfunction "2_2") (pintype "passive"))
      (node (ref "C77") (pin "2") (pinfunction "2_2") (pintype "passive"))
      (node (ref "C78") (pin "2") (pinfunction "2_2") (pintype "passive"))
      (node (ref "C79") (pin "2") (pinfunction "2_2") (pintype "passive"))
      (node (ref "C80") (pin "2") (pinfunction "2_2") (pintype "passive"))
      (node (ref "C81") (pin "2") (pinfunction "2_2") (pintype "passive"))
      (node (ref "C87") (pin "2") (pinfunction "2_2") (pintype "passive"))
      (node (ref "C92") (pin "1") (pinfunction "1_1") (pintype "passive"))
      (node (ref "C99") (pin "1") (pinfunction "1_1") (pintype "passive"))
      (node (ref "JP9") (pin "2") (pinfunction "2_2") (pintype "passive"))
      (node (ref "O3") (pin "4") (pinfunction "V+_4") (pintype "bidirectional"))
      (node (ref "R29") (pin "1") (pinfunction "1_1") (pintype "passive"))
      (node (ref "S1") (pin "1") (pinfunction "A1_1") (pintype "passive"))
      (node (ref "S1") (pin "2") (pinfunction "A2_2") (pintype "passive"))
      (node (ref "S1") (pin "3") (pinfunction "A3_3") (pintype "passive"))
      (node (ref "S1") (pin "4") (pinfunction "A4_4") (pintype "passive"))
      (node (ref "S1") (pin "5") (pinfunction "A5_5") (pintype "passive"))
      (node (ref "S1") (pin "6") (pinfunction "A6_6") (pintype "passive"))
      (node (ref "S1") (pin "7") (pinfunction "A7_7") (pintype "passive"))
      (node (ref "S1") (pin "8") (pinfunction "A8_8") (pintype "passive"))
      (node (ref "U2") (pin "1") (pinfunction "EN_1") (pintype "input"))
      (node (ref "U2") (pin "2") (pinfunction "IN_2") (pintype "power_in"))
      (node (ref "U22") (pin "26") (pinfunction "VCCIO_26") (pintype "power_in"))
      (node (ref "U22") (pin "35") (pinfunction "Vaux_35") (pintype "power_in"))
      (node (ref "U22") (pin "7") (pinfunction "VCCIO_7") (pintype "power_in"))
      (node (ref "U23") (pin "1") (pinfunction "EN_1") (pintype "input"))
      (node (ref "U23") (pin "2") (pinfunction "IN_2") (pintype "power_in"))
      (node (ref "U25") (pin "1") (pinfunction "EN_1") (pintype "input"))
      (node (ref "U25") (pin "2") (pinfunction "IN_2") (pintype "power_in"))
      (node (ref "U3") (pin "10") (pinfunction "VDD_10") (pintype "power_in"))
      (node (ref "U3") (pin "13") (pinfunction "VDD_13") (pintype "power_in"))
    )
    (net (code "40") (name "unconnected-(JP9-Pad12)") (class "Default")
      (node (ref "JP9") (pin "12") (pinfunction "12_12") (pintype "passive+no_connect"))
    )
    (net (code "41") (name "unconnected-(JP9-Pad14)") (class "Default")
      (node (ref "JP9") (pin "14") (pinfunction "14_14") (pintype "passive+no_connect"))
    )
    (net (code "42") (name "unconnected-(O3-OE-Pad1)") (class "Default")
      (node (ref "O3") (pin "1") (pinfunction "OE_1") (pintype "bidirectional"))
    )
    (net (code "43") (name "unconnected-(S1-B6-Pad11)") (class "Default")
      (node (ref "S1") (pin "11") (pinfunction "B6_11") (pintype "passive"))
    )
    (net (code "44") (name "unconnected-(U3-M6-Pad2)") (class "Default")
      (node (ref "U3") (pin "2") (pinfunction "M6_2") (pintype "input"))
    )
    (net (code "45") (name "unconnected-(U3-M7-Pad3)") (class "Default")
      (node (ref "U3") (pin "3") (pinfunction "M7_3") (pintype "input"))
    )
    (net (code "46") (name "unconnected-(U3-M8-Pad4)") (class "Default")
      (node (ref "U3") (pin "4") (pinfunction "M8_4") (pintype "input"))
    )
    (net (code "47") (name "unconnected-(U3-S_CLOCK-Pad18)") (class "Default")
      (node (ref "U3") (pin "18") (pinfunction "S_CLOCK_18") (pintype "input"))
    )
    (net (code "48") (name "unconnected-(U3-S_DATA-Pad19)") (class "Default")
      (node (ref "U3") (pin "19") (pinfunction "S_DATA_19") (pintype "input"))
    )
    (net (code "49") (name "unconnected-(U3-S_LOAD-Pad20)") (class "Default")
      (node (ref "U3") (pin "20") (pinfunction "S_LOAD_20") (pintype "input"))
    )
    (net (code "50") (name "unconnected-(U3-TEST_CLK-Pad23)") (class "Default")
      (node (ref "U3") (pin "23") (pinfunction "TEST_CLK_23") (pintype "input"))
    )
    (net (code "51") (name "unconnected-(U3-VCO_SEL-Pad27)") (class "Default")
      (node (ref "U3") (pin "27") (pinfunction "VCO_SEL_27") (pintype "input"))
    )
    (net (code "52") (name "unconnected-(U3-XTAL_SEL-Pad22)") (class "Default")
      (node (ref "U3") (pin "22") (pinfunction "XTAL_SEL_22") (pintype "input"))
    )
    (net (code "53") (name "unconnected-(U22-FB1-GSR-Pad30)") (class "Default")
      (node (ref "U22") (pin "30") (pinfunction "FB1-GSR_30") (pintype "bidirectional"))
    )
    (net (code "54") (name "unconnected-(U22-FB1-GTS0-Pad33)") (class "Default")
      (node (ref "U22") (pin "33") (pinfunction "FB1-GTS0_33") (pintype "bidirectional"))
    )
    (net (code "55") (name "unconnected-(U22-FB1-GTS1-Pad34)") (class "Default")
      (node (ref "U22") (pin "34") (pinfunction "FB1-GTS1_34") (pintype "bidirectional"))
    )
    (net (code "56") (name "unconnected-(U22-FB1-GTS2-Pad31)") (class "Default")
      (node (ref "U22") (pin "31") (pinfunction "FB1-GTS2_31") (pintype "bidirectional"))
    )
    (net (code "57") (name "unconnected-(U22-FB1-GTS3-Pad32)") (class "Default")
      (node (ref "U22") (pin "32") (pinfunction "FB1-GTS3_32") (pintype "bidirectional"))
    )
    (net (code "58") (name "unconnected-(U22-FB2-GCK0-Pad43)") (class "Default")
      (node (ref "U22") (pin "43") (pinfunction "FB2-GCK0_43") (pintype "bidirectional"))
    )
    (net (code "59") (name "unconnected-(U22-FB2-GCK1-Pad44)") (class "Default")
      (node (ref "U22") (pin "44") (pinfunction "FB2-GCK1_44") (pintype "bidirectional"))
    )
    (net (code "60") (name "unconnected-(U22-FB2M5-Pad41)") (class "Default")
      (node (ref "U22") (pin "41") (pinfunction "FB2M5_41") (pintype "bidirectional"))
    )
    (net (code "61") (name "unconnected-(U22-FB2M6-Pad42)") (class "Default")
      (node (ref "U22") (pin "42") (pinfunction "FB2M6_42") (pintype "bidirectional"))
    )
    (net (code "62") (name "unconnected-(U22-FB2M12-Pad2)") (class "Default")
      (node (ref "U22") (pin "2") (pinfunction "FB2M12_2") (pintype "bidirectional"))
    )
    (net (code "63") (name "unconnected-(U22-FB2M13-Pad3)") (class "Default")
      (node (ref "U22") (pin "3") (pinfunction "FB2M13_3") (pintype "bidirectional"))
    )
    (net (code "64") (name "unconnected-(U22-FB3M1-Pad29)") (class "Default")
      (node (ref "U22") (pin "29") (pinfunction "FB3M1_29") (pintype "bidirectional"))
    )
    (net (code "65") (name "unconnected-(U22-FB3M2-Pad28)") (class "Default")
      (node (ref "U22") (pin "28") (pinfunction "FB3M2_28") (pintype "bidirectional"))
    )
    (net (code "66") (name "unconnected-(U22-FB3M3-Pad27)") (class "Default")
      (node (ref "U22") (pin "27") (pinfunction "FB3M3_27") (pintype "bidirectional"))
    )
    (net (code "67") (name "unconnected-(U22-FB3M6-Pad23)") (class "Default")
      (node (ref "U22") (pin "23") (pinfunction "FB3M6_23") (pintype "bidirectional"))
    )
    (net (code "68") (name "unconnected-(U22-FB3M10-Pad22)") (class "Default")
      (node (ref "U22") (pin "22") (pinfunction "FB3M10_22") (pintype "bidirectional"))
    )
    (net (code "69") (name "unconnected-(U22-FB3M11-Pad21)") (class "Default")
      (node (ref "U22") (pin "21") (pinfunction "FB3M11_21") (pintype "bidirectional"))
    )
    (net (code "70") (name "unconnected-(U22-FB3M12-Pad20)") (class "Default")
      (node (ref "U22") (pin "20") (pinfunction "FB3M12_20") (pintype "bidirectional"))
    )
    (net (code "71") (name "unconnected-(U22-FB3M14-Pad19)") (class "Default")
      (node (ref "U22") (pin "19") (pinfunction "FB3M14_19") (pintype "bidirectional"))
    )
    (net (code "72") (name "unconnected-(U22-FB3M15-Pad18)") (class "Default")
      (node (ref "U22") (pin "18") (pinfunction "FB3M15_18") (pintype "bidirectional"))
    )
    (net (code "73") (name "unconnected-(U22-FB4M1-Pad5)") (class "Default")
      (node (ref "U22") (pin "5") (pinfunction "FB4M1_5") (pintype "bidirectional"))
    )
    (net (code "74") (name "unconnected-(U22-FB4M2-Pad6)") (class "Default")
      (node (ref "U22") (pin "6") (pinfunction "FB4M2_6") (pintype "bidirectional"))
    )
    (net (code "75") (name "unconnected-(U22-FB4M11-Pad12)") (class "Default")
      (node (ref "U22") (pin "12") (pinfunction "FB4M11_12") (pintype "bidirectional"))
    )
    (net (code "76") (name "unconnected-(U22-FB4M13-Pad13)") (class "Default")
      (node (ref "U22") (pin "13") (pinfunction "FB4M13_13") (pintype "bidirectional"))
    )
    (net (code "77") (name "unconnected-(U22-FB4M14-Pad14)") (class "Default")
      (node (ref "U22") (pin "14") (pinfunction "FB4M14_14") (pintype "bidirectional"))
    )
    (net (code "78") (name "unconnected-(U22-FB4M15-Pad16)") (class "Default")
      (node (ref "U22") (pin "16") (pinfunction "FB4M15_16") (pintype "bidirectional"))
    )
  )
)
